# Codec.net
KiCad netlist of a schematic drawn in Altium Designer
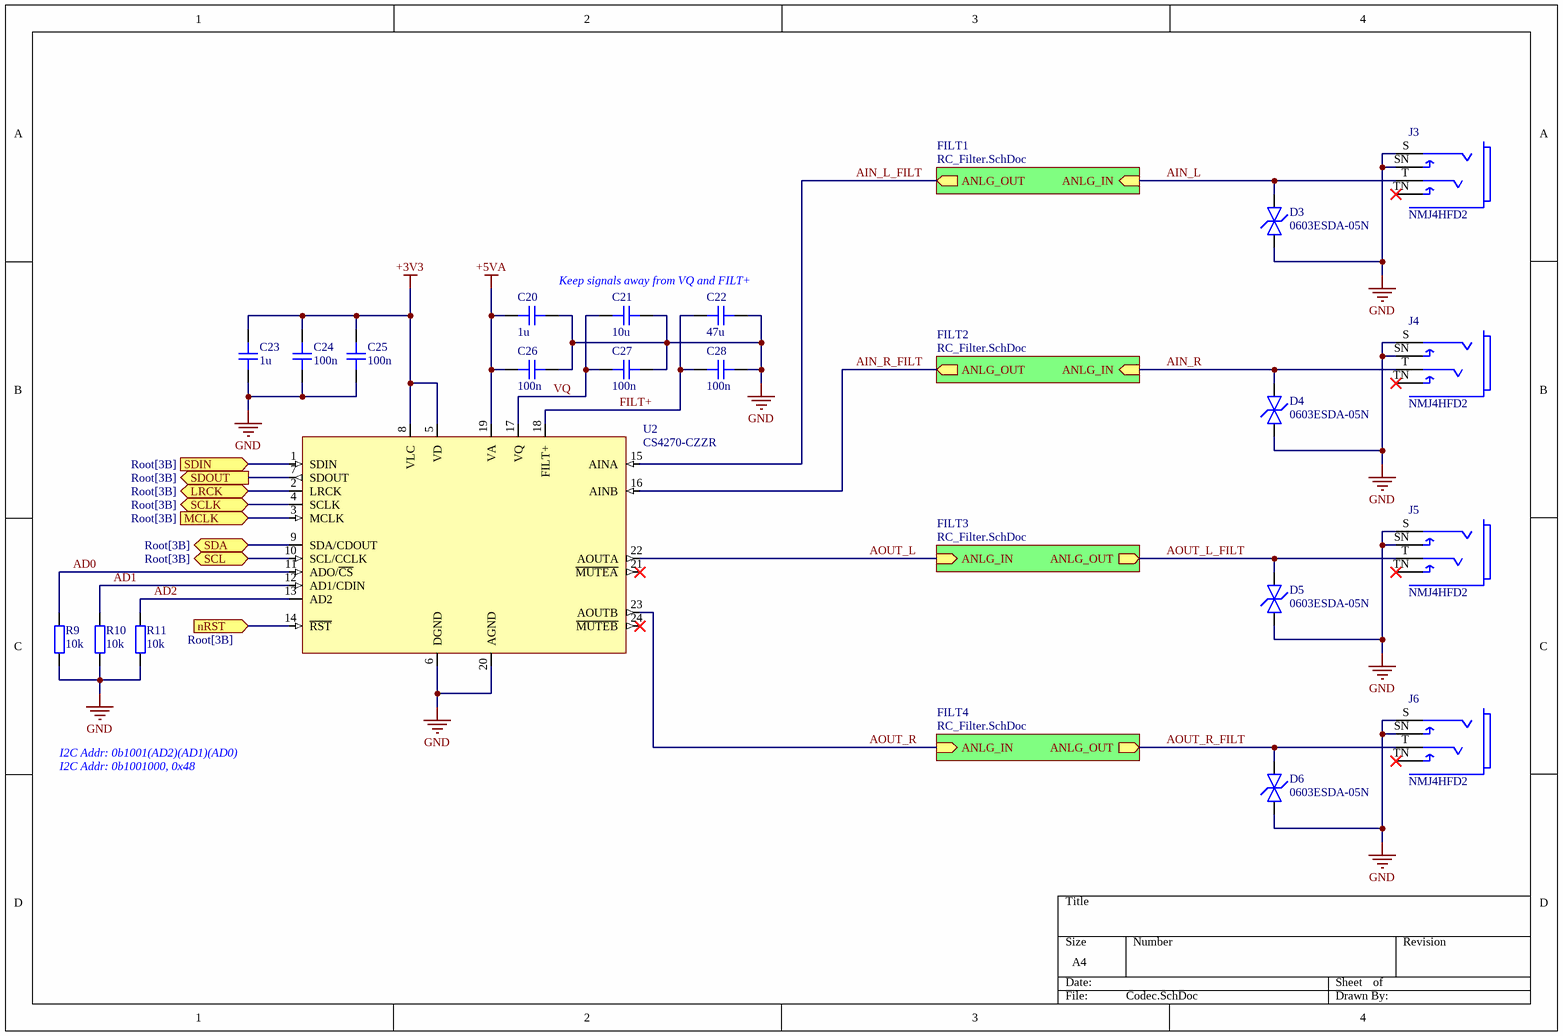
[diagram p0: Codec.SchDoc]

(export (version "E")
  (design (tool "Eeschema 10.0.6"))
  (components
    (comp (ref "C20")
      (value "1u")
      (footprint "CAP_0603")
      (description "Capacitor SMD 0603")
      (libsource (lib "Schematic-Lib-PhilsLab") (part "CAP_0603"))
    )
    (comp (ref "C21")
      (value "10u")
      (footprint "CAP_1210")
      (description "Capacitor SMD 1210")
      (libsource (lib "Schematic-Lib-PhilsLab") (part "CAP_1210"))
    )
    (comp (ref "C22")
      (value "47u")
      (footprint "CAP_1210")
      (description "Capacitor SMD 1210")
      (libsource (lib "Schematic-Lib-PhilsLab") (part "CAP_1210"))
    )
    (comp (ref "C23")
      (value "1u")
      (footprint "CAP_0603")
      (description "Capacitor SMD 0603")
      (libsource (lib "Schematic-Lib-PhilsLab") (part "CAP_0603"))
    )
    (comp (ref "C24")
      (value "100n")
      (footprint "CAP_0603")
      (description "Capacitor SMD 0603")
      (libsource (lib "Schematic-Lib-PhilsLab") (part "CAP_0603"))
    )
    (comp (ref "C25")
      (value "100n")
      (footprint "CAP_0603")
      (description "Capacitor SMD 0603")
      (libsource (lib "Schematic-Lib-PhilsLab") (part "CAP_0603"))
    )
    (comp (ref "C26")
      (value "100n")
      (footprint "CAP_0603")
      (description "Capacitor SMD 0603")
      (libsource (lib "Schematic-Lib-PhilsLab") (part "CAP_0603"))
    )
    (comp (ref "C27")
      (value "100n")
      (footprint "CAP_0603")
      (description "Capacitor SMD 0603")
      (libsource (lib "Schematic-Lib-PhilsLab") (part "CAP_0603"))
    )
    (comp (ref "C28")
      (value "100n")
      (footprint "CAP_0603")
      (description "Capacitor SMD 0603")
      (libsource (lib "Schematic-Lib-PhilsLab") (part "CAP_0603"))
    )
    (comp (ref "D3")
      (value "0603ESDA-05N")
      (footprint "D_0603")
      (description "Diode TVS / ESD Bidirectional 0603")
      (libsource (lib "Schematic-Lib-PhilsLab") (part "D_TVS_BI_0603"))
    )
    (comp (ref "D4")
      (value "0603ESDA-05N")
      (footprint "D_0603")
      (description "Diode TVS / ESD Bidirectional 0603")
      (libsource (lib "Schematic-Lib-PhilsLab") (part "D_TVS_BI_0603"))
    )
    (comp (ref "D5")
      (value "0603ESDA-05N")
      (footprint "D_0603")
      (description "Diode TVS / ESD Bidirectional 0603")
      (libsource (lib "Schematic-Lib-PhilsLab") (part "D_TVS_BI_0603"))
    )
    (comp (ref "D6")
      (value "0603ESDA-05N")
      (footprint "D_0603")
      (description "Diode TVS / ESD Bidirectional 0603")
      (libsource (lib "Schematic-Lib-PhilsLab") (part "D_TVS_BI_0603"))
    )
    (comp (ref "J3")
      (value "NMJ4HFD2")
      (footprint "FP-NMJ4HFD2-MFG")
      (description "Conn 1/4\" Mono Jack F 3 POS Solder RA Thru-Hole 3 Terminal 1 Port")
      (fields
        (field (name "MANUFACTURER") "Neutrik")
        (field (name "OCTOPART") "https://octopart.com/nmj4hfd2-neutrik-758952")
      )
      (libsource (lib "Altium Content Vault") (part "8c9933f05338f077543a5425baeefa5"))
    )
    (comp (ref "J4")
      (value "NMJ4HFD2")
      (footprint "FP-NMJ4HFD2-MFG")
      (description "Conn 1/4\" Mono Jack F 3 POS Solder RA Thru-Hole 3 Terminal 1 Port")
      (fields
        (field (name "MANUFACTURER") "Neutrik")
        (field (name "OCTOPART") "https://octopart.com/nmj4hfd2-neutrik-758952")
      )
      (libsource (lib "Altium Content Vault") (part "8c9933f05338f077543a5425baeefa5"))
    )
    (comp (ref "J5")
      (value "NMJ4HFD2")
      (footprint "FP-NMJ4HFD2-MFG")
      (description "Conn 1/4\" Mono Jack F 3 POS Solder RA Thru-Hole 3 Terminal 1 Port")
      (fields
        (field (name "MANUFACTURER") "Neutrik")
        (field (name "OCTOPART") "https://octopart.com/nmj4hfd2-neutrik-758952")
      )
      (libsource (lib "Altium Content Vault") (part "8c9933f05338f077543a5425baeefa5"))
    )
    (comp (ref "J6")
      (value "NMJ4HFD2")
      (footprint "FP-NMJ4HFD2-MFG")
      (description "Conn 1/4\" Mono Jack F 3 POS Solder RA Thru-Hole 3 Terminal 1 Port")
      (fields
        (field (name "MANUFACTURER") "Neutrik")
        (field (name "OCTOPART") "https://octopart.com/nmj4hfd2-neutrik-758952")
      )
      (libsource (lib "Altium Content Vault") (part "8c9933f05338f077543a5425baeefa5"))
    )
    (comp (ref "R9")
      (value "10k")
      (footprint "RES_0603")
      (description "Resistor SMD 0603")
      (libsource (lib "Schematic-Lib-PhilsLab") (part "RES_0603"))
    )
    (comp (ref "R10")
      (value "10k")
      (footprint "RES_0603")
      (description "Resistor SMD 0603")
      (libsource (lib "Schematic-Lib-PhilsLab") (part "RES_0603"))
    )
    (comp (ref "R11")
      (value "10k")
      (footprint "RES_0603")
      (description "Resistor SMD 0603")
      (libsource (lib "Schematic-Lib-PhilsLab") (part "RES_0603"))
    )
    (comp (ref "U2")
      (value "CS4270-CZZR")
      (footprint "TSSOP-24")
      (description "24-Bit 192kHz Stereo Audio Codec TSSOP-24")
      (fields (field (name "MANUFACTURER") "Cirrus Logic"))
      (libsource (lib "Schematic-Lib-PhilsLab") (part "CS4270-CZZR"))
    )
  )
  (nets
    (net (code "1") (name "+3V3") (class "Default")
      (node (ref "C23") (pin "2") (pinfunction "2_2") (pintype "passive"))
      (node (ref "C24") (pin "1") (pinfunction "1_1") (pintype "passive"))
      (node (ref "C25") (pin "1") (pinfunction "1_1") (pintype "passive"))
      (node (ref "U2") (pin "5") (pinfunction "VD_5") (pintype "power_in"))
      (node (ref "U2") (pin "8") (pinfunction "VLC_8") (pintype "power_in"))
    )
    (net (code "2") (name "+5VA") (class "Default")
      (node (ref "C20") (pin "1") (pinfunction "1_1") (pintype "passive"))
      (node (ref "C26") (pin "2") (pinfunction "2_2") (pintype "passive"))
      (node (ref "U2") (pin "19") (pinfunction "VA_19") (pintype "power_in"))
    )
    (net (code "3") (name "/AD0") (class "Default")
      (node (ref "R9") (pin "2") (pinfunction "2_2") (pintype "passive"))
      (node (ref "U2") (pin "11") (pinfunction "ADO/~{CS}_11") (pintype "input"))
    )
    (net (code "4") (name "/AD1") (class "Default")
      (node (ref "R10") (pin "2") (pinfunction "2_2") (pintype "passive"))
      (node (ref "U2") (pin "12") (pinfunction "AD1/CDIN_12") (pintype "input"))
    )
    (net (code "5") (name "/AD2") (class "Default")
      (node (ref "R11") (pin "2") (pinfunction "2_2") (pintype "passive"))
      (node (ref "U2") (pin "13") (pinfunction "AD2_13") (pintype "passive"))
    )
    (net (code "6") (name "/AIN_L") (class "Default")
      (node (ref "D3") (pin "K") (pinfunction "K_K") (pintype "passive"))
      (node (ref "J3") (pin "T") (pinfunction "T_T") (pintype "passive"))
    )
    (net (code "7") (name "/AIN_L_FILT") (class "Default")
      (node (ref "U2") (pin "15") (pinfunction "AINA_15") (pintype "input"))
    )
    (net (code "8") (name "/AIN_R") (class "Default")
      (node (ref "D4") (pin "K") (pinfunction "K_K") (pintype "passive"))
      (node (ref "J4") (pin "T") (pinfunction "T_T") (pintype "passive"))
    )
    (net (code "9") (name "/AIN_R_FILT") (class "Default")
      (node (ref "U2") (pin "16") (pinfunction "AINB_16") (pintype "input"))
    )
    (net (code "10") (name "/AOUT_L") (class "Default")
      (node (ref "U2") (pin "22") (pinfunction "AOUTA_22") (pintype "output"))
    )
    (net (code "11") (name "/AOUT_L_FILT") (class "Default")
      (node (ref "D5") (pin "K") (pinfunction "K_K") (pintype "passive"))
      (node (ref "J5") (pin "T") (pinfunction "T_T") (pintype "passive"))
    )
    (net (code "12") (name "/AOUT_R") (class "Default")
      (node (ref "U2") (pin "23") (pinfunction "AOUTB_23") (pintype "output"))
    )
    (net (code "13") (name "/AOUT_R_FILT") (class "Default")
      (node (ref "D6") (pin "K") (pinfunction "K_K") (pintype "passive"))
      (node (ref "J6") (pin "T") (pinfunction "T_T") (pintype "passive"))
    )
    (net (code "14") (name "/FILT+") (class "Default")
      (node (ref "C22") (pin "1") (pinfunction "1_1") (pintype "passive"))
      (node (ref "C28") (pin "1") (pinfunction "1_1") (pintype "passive"))
      (node (ref "U2") (pin "18") (pinfunction "FILT+_18") (pintype "power_in"))
    )
    (net (code "15") (name "/LRCK") (class "Default")
      (node (ref "U2") (pin "2") (pinfunction "LRCK_2") (pintype "bidirectional"))
    )
    (net (code "16") (name "/MCLK") (class "Default")
      (node (ref "U2") (pin "3") (pinfunction "MCLK_3") (pintype "input"))
    )
    (net (code "17") (name "/SCL") (class "Default")
      (node (ref "U2") (pin "10") (pinfunction "SCL/CCLK_10") (pintype "input"))
    )
    (net (code "18") (name "/SCLK") (class "Default")
      (node (ref "U2") (pin "4") (pinfunction "SCLK_4") (pintype "bidirectional"))
    )
    (net (code "19") (name "/SDA") (class "Default")
      (node (ref "U2") (pin "9") (pinfunction "SDA/CDOUT_9") (pintype "bidirectional"))
    )
    (net (code "20") (name "/SDIN") (class "Default")
      (node (ref "U2") (pin "1") (pinfunction "SDIN_1") (pintype "input"))
    )
    (net (code "21") (name "/SDOUT") (class "Default")
      (node (ref "U2") (pin "7") (pinfunction "SDOUT_7") (pintype "output"))
    )
    (net (code "22") (name "/VQ") (class "Default")
      (node (ref "C21") (pin "1") (pinfunction "1_1") (pintype "passive"))
      (node (ref "C27") (pin "1") (pinfunction "1_1") (pintype "passive"))
      (node (ref "U2") (pin "17") (pinfunction "VQ_17") (pintype "power_in"))
    )
    (net (code "23") (name "/nRST") (class "Default")
      (node (ref "U2") (pin "14") (pinfunction "~{RST}_14") (pintype "input"))
    )
    (net (code "24") (name "GND") (class "Default")
      (node (ref "C20") (pin "2") (pinfunction "2_2") (pintype "passive"))
      (node (ref "C21") (pin "2") (pinfunction "2_2") (pintype "passive"))
      (node (ref "C22") (pin "2") (pinfunction "2_2") (pintype "passive"))
      (node (ref "C23") (pin "1") (pinfunction "1_1") (pintype "passive"))
      (node (ref "C24") (pin "2") (pinfunction "2_2") (pintype "passive"))
      (node (ref "C25") (pin "2") (pinfunction "2_2") (pintype "passive"))
      (node (ref "C26") (pin "1") (pinfunction "1_1") (pintype "passive"))
      (node (ref "C27") (pin "2") (pinfunction "2_2") (pintype "passive"))
      (node (ref "C28") (pin "2") (pinfunction "2_2") (pintype "passive"))
      (node (ref "D3") (pin "A") (pinfunction "A_A") (pintype "passive"))
      (node (ref "D4") (pin "A") (pinfunction "A_A") (pintype "passive"))
      (node (ref "D5") (pin "A") (pinfunction "A_A") (pintype "passive"))
      (node (ref "D6") (pin "A") (pinfunction "A_A") (pintype "passive"))
      (node (ref "J3") (pin "S") (pinfunction "S_S") (pintype "passive"))
      (node (ref "J3") (pin "SN") (pinfunction "SN_SN") (pintype "passive"))
      (node (ref "J4") (pin "S") (pinfunction "S_S") (pintype "passive"))
      (node (ref "J4") (pin "SN") (pinfunction "SN_SN") (pintype "passive"))
      (node (ref "J5") (pin "S") (pinfunction "S_S") (pintype "passive"))
      (node (ref "J5") (pin "SN") (pinfunction "SN_SN") (pintype "passive"))
      (node (ref "J6") (pin "S") (pinfunction "S_S") (pintype "passive"))
      (node (ref "J6") (pin "SN") (pinfunction "SN_SN") (pintype "passive"))
      (node (ref "R10") (pin "1") (pinfunction "1_1") (pintype "passive"))
      (node (ref "R11") (pin "1") (pinfunction "1_1") (pintype "passive"))
      (node (ref "R9") (pin "1") (pinfunction "1_1") (pintype "passive"))
      (node (ref "U2") (pin "20") (pinfunction "AGND_20") (pintype "power_in"))
      (node (ref "U2") (pin "6") (pinfunction "DGND_6") (pintype "power_in"))
    )
    (net (code "25") (name "unconnected-(J3-PadTN)") (class "Default")
      (node (ref "J3") (pin "TN") (pinfunction "TN_TN") (pintype "passive+no_connect"))
    )
    (net (code "26") (name "unconnected-(J4-PadTN)") (class "Default")
      (node (ref "J4") (pin "TN") (pinfunction "TN_TN") (pintype "passive+no_connect"))
    )
    (net (code "27") (name "unconnected-(J5-PadTN)") (class "Default")
      (node (ref "J5") (pin "TN") (pinfunction "TN_TN") (pintype "passive+no_connect"))
    )
    (net (code "28") (name "unconnected-(J6-PadTN)") (class "Default")
      (node (ref "J6") (pin "TN") (pinfunction "TN_TN") (pintype "passive+no_connect"))
    )
    (net (code "29") (name "unconnected-(U2-~{MUTEA}-Pad21)") (class "Default")
      (node (ref "U2") (pin "21") (pinfunction "~{MUTEA}_21") (pintype "output+no_connect"))
    )
    (net (code "30") (name "unconnected-(U2-~{MUTEB}-Pad24)") (class "Default")
      (node (ref "U2") (pin "24") (pinfunction "~{MUTEB}_24") (pintype "output+no_connect"))
    )
  )
)
